# T04_Main_Board.net
KiCad netlist of a schematic drawn in EAGLE
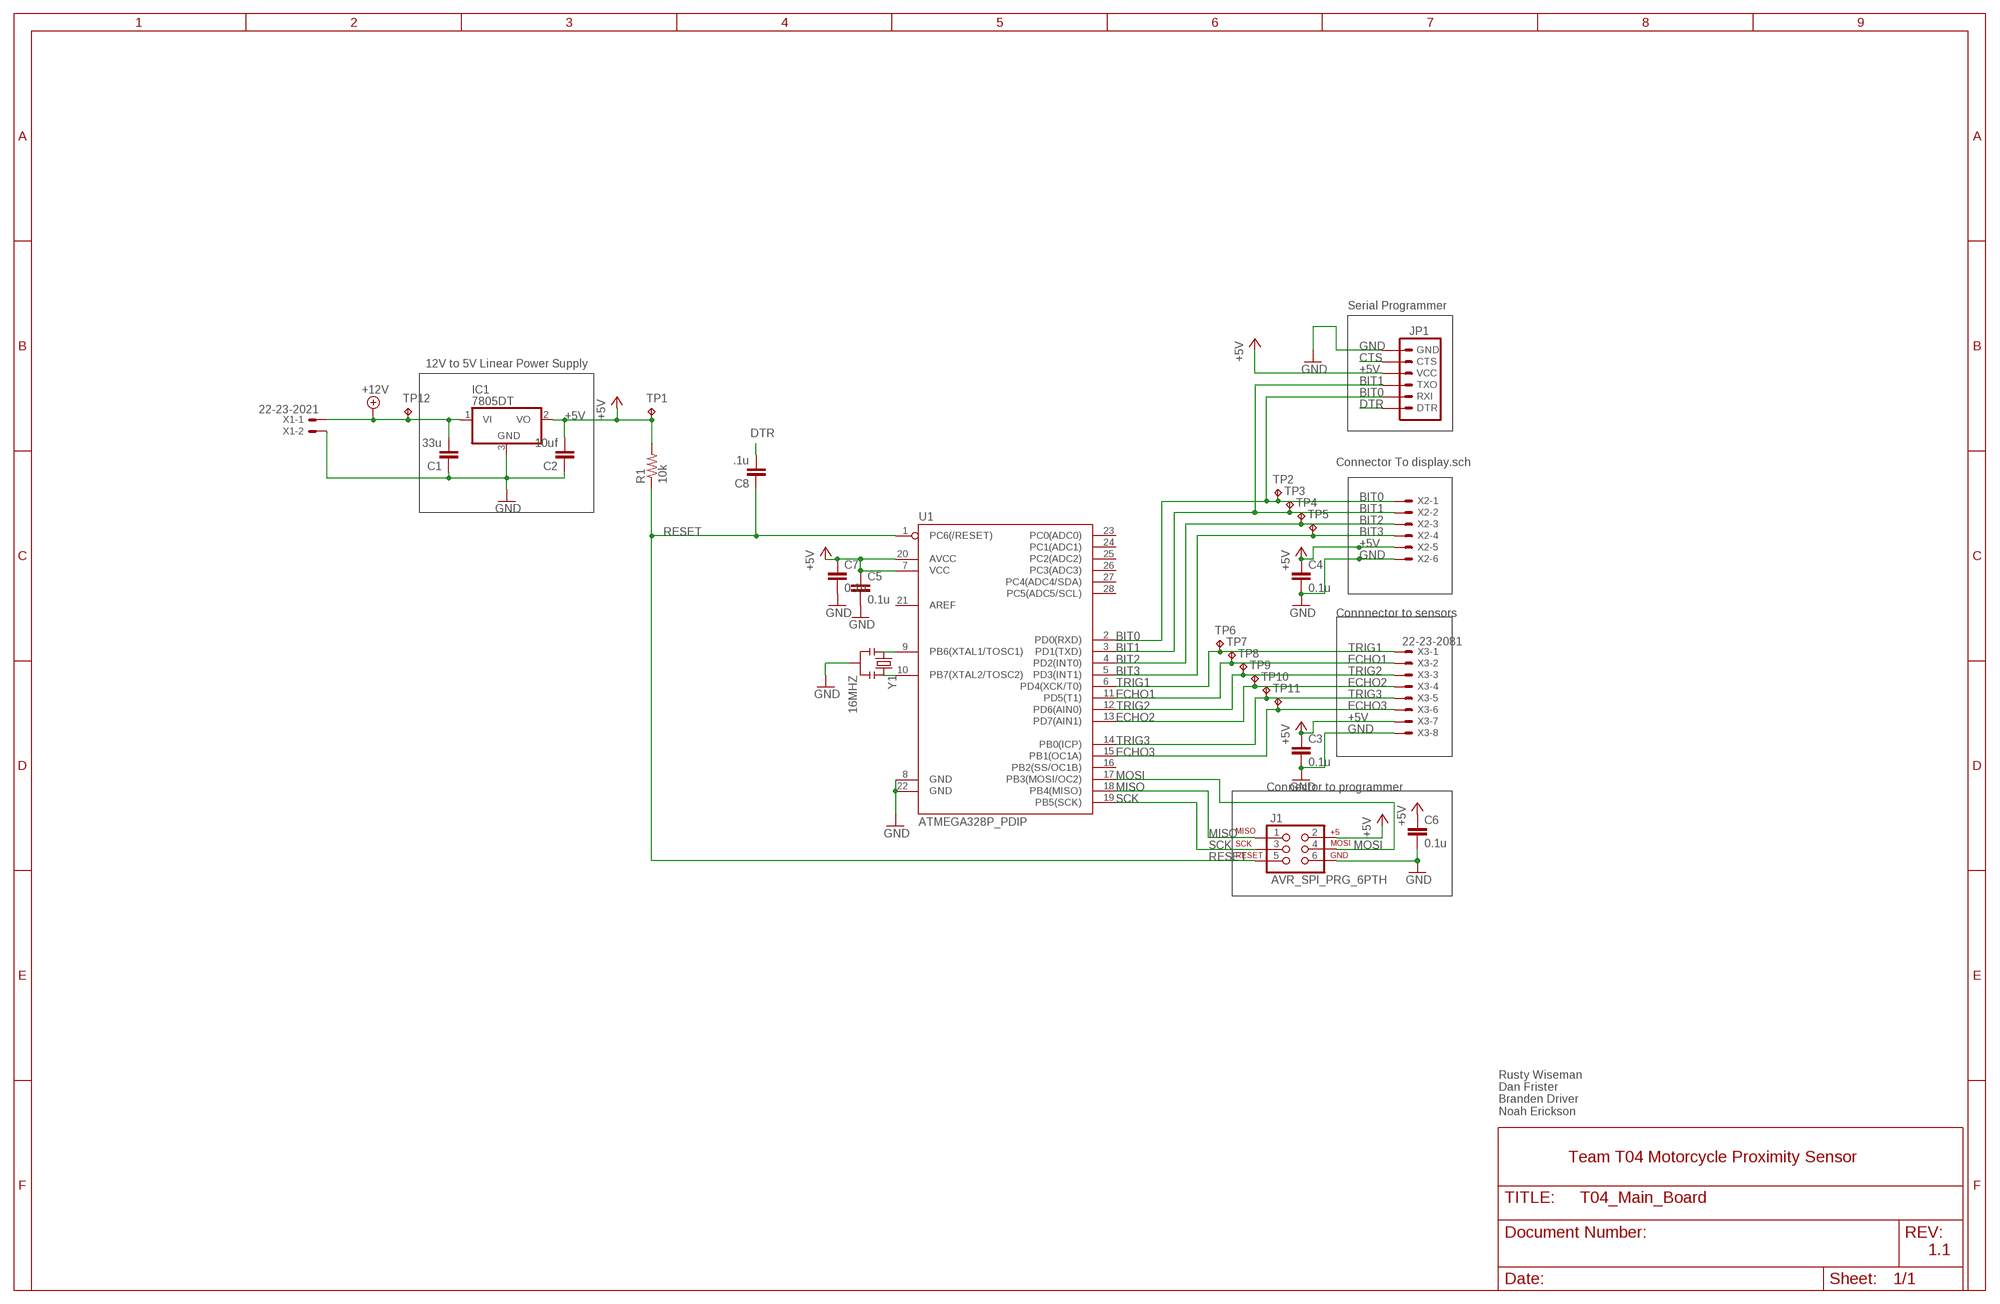
[diagram p0: schematic, sheet 1]

(export (version "E")
  (design (tool "Eeschema 10.0.6"))
  (components
    (comp (ref "C1")
      (value "33u")
      (footprint "eagle-import:C025-024X044")
      (libsource (lib "eagle-import") (part "C-EU025-024X044"))
    )
    (comp (ref "C2")
      (value "10uf")
      (footprint "eagle-import:C025-024X044")
      (libsource (lib "eagle-import") (part "C-EU025-024X044"))
    )
    (comp (ref "C3")
      (value "0.1u")
      (footprint "eagle-import:C025-024X044")
      (libsource (lib "eagle-import") (part "C-EU025-024X044"))
    )
    (comp (ref "C4")
      (value "0.1u")
      (footprint "eagle-import:C025-024X044")
      (libsource (lib "eagle-import") (part "C-EU025-024X044"))
    )
    (comp (ref "C5")
      (value "0.1u")
      (footprint "eagle-import:C025-024X044")
      (libsource (lib "eagle-import") (part "C-EU025-024X044"))
    )
    (comp (ref "C6")
      (value "0.1u")
      (footprint "eagle-import:C025-024X044")
      (libsource (lib "eagle-import") (part "C-EU025-024X044"))
    )
    (comp (ref "C7")
      (value "0.1u")
      (footprint "eagle-import:C025-024X044")
      (libsource (lib "eagle-import") (part "C-EU025-024X044"))
    )
    (comp (ref "C8")
      (value ".1u")
      (footprint "eagle-import:C025-024X044")
      (libsource (lib "eagle-import") (part "C-EU025-024X044"))
    )
    (comp (ref "IC1")
      (value "7805DT")
      (footprint "eagle-import:TO252")
      (libsource (lib "eagle-import") (part "78DT05"))
    )
    (comp (ref "J1")
      (value "AVR_SPI_PRG_6PTH")
      (footprint "eagle-import:2X3")
      (libsource (lib "eagle-import") (part "AVR_SPI_PRG_6PTH"))
    )
    (comp (ref "JP1")
      (value "ARDUINO_SERIAL_PROGRAMSMD")
      (footprint "eagle-import:1X06-SMD")
      (libsource (lib "eagle-import") (part "ARDUINO_SERIAL_PROGRAMSMD"))
    )
    (comp (ref "R1")
      (value "10k")
      (footprint "eagle-import:M2309")
      (libsource (lib "eagle-import") (part "R-US_M2309"))
    )
    (comp (ref "TP1")
      (value "TPB1,27")
      (footprint "eagle-import:B1,27")
      (libsource (lib "eagle-import") (part "TPB1,27"))
    )
    (comp (ref "TP2")
      (value "TPB1,27")
      (footprint "eagle-import:B1,27")
      (libsource (lib "eagle-import") (part "TPB1,27"))
    )
    (comp (ref "TP3")
      (value "TPB1,27")
      (footprint "eagle-import:B1,27")
      (libsource (lib "eagle-import") (part "TPB1,27"))
    )
    (comp (ref "TP4")
      (value "TPB1,27")
      (footprint "eagle-import:B1,27")
      (libsource (lib "eagle-import") (part "TPB1,27"))
    )
    (comp (ref "TP5")
      (value "TPB1,27")
      (footprint "eagle-import:B1,27")
      (libsource (lib "eagle-import") (part "TPB1,27"))
    )
    (comp (ref "TP6")
      (value "TPB1,27")
      (footprint "eagle-import:B1,27")
      (libsource (lib "eagle-import") (part "TPB1,27"))
    )
    (comp (ref "TP7")
      (value "TPB1,27")
      (footprint "eagle-import:B1,27")
      (libsource (lib "eagle-import") (part "TPB1,27"))
    )
    (comp (ref "TP8")
      (value "TPB1,27")
      (footprint "eagle-import:B1,27")
      (libsource (lib "eagle-import") (part "TPB1,27"))
    )
    (comp (ref "TP9")
      (value "TPB1,27")
      (footprint "eagle-import:B1,27")
      (libsource (lib "eagle-import") (part "TPB1,27"))
    )
    (comp (ref "TP10")
      (value "TPB1,27")
      (footprint "eagle-import:B1,27")
      (libsource (lib "eagle-import") (part "TPB1,27"))
    )
    (comp (ref "TP11")
      (value "TPB1,27")
      (footprint "eagle-import:B1,27")
      (libsource (lib "eagle-import") (part "TPB1,27"))
    )
    (comp (ref "TP12")
      (value "TPB1,27")
      (footprint "eagle-import:B1,27")
      (libsource (lib "eagle-import") (part "TPB1,27"))
    )
    (comp (ref "U1")
      (value "ATMEGA328P_PDIP")
      (footprint "eagle-import:DIL28-3")
      (libsource (lib "eagle-import") (part "ATMEGA328P_PDIP"))
    )
    (comp (ref "X1")
      (value "22-23-2021")
      (footprint "eagle-import:22-23-2021")
      (fields (field (name "MF") "MOLEX"))
      (libsource (lib "eagle-import") (part "22-23-2021"))
    )
    (comp (ref "X2")
      (value "22-23-2061")
      (footprint "eagle-import:22-23-2061")
      (fields (field (name "MF") "MOLEX"))
      (libsource (lib "eagle-import") (part "22-23-2061"))
    )
    (comp (ref "X3")
      (value "22-23-2081")
      (footprint "eagle-import:22-23-2081")
      (fields (field (name "MF") "MOLEX"))
      (libsource (lib "eagle-import") (part "22-23-2081"))
    )
    (comp (ref "Y1")
      (value "16MHZ")
      (footprint "eagle-import:RESONATOR-SMD")
      (libsource (lib "eagle-import") (part "RESONATOR16MHZ"))
    )
  )
  (nets
    (net (code "1") (name "+5V") (class "Default")
      (node (ref "C2") (pin "2") (pinfunction "2_2") (pintype "passive"))
      (node (ref "C3") (pin "1") (pinfunction "1_1") (pintype "passive"))
      (node (ref "C4") (pin "1") (pinfunction "1_1") (pintype "passive"))
      (node (ref "C5") (pin "1") (pinfunction "1_1") (pintype "passive"))
      (node (ref "C6") (pin "1") (pinfunction "1_1") (pintype "passive"))
      (node (ref "C7") (pin "1") (pinfunction "1_1") (pintype "passive"))
      (node (ref "IC1") (pin "2") (pinfunction "VO_2") (pintype "passive"))
      (node (ref "J1") (pin "2") (pinfunction "2_2") (pintype "passive"))
      (node (ref "JP1") (pin "4") (pinfunction "VCC_4") (pintype "passive"))
      (node (ref "R1") (pin "2") (pinfunction "2_2") (pintype "passive"))
      (node (ref "TP1") (pin "TP") (pinfunction "TP_TP") (pintype "input"))
      (node (ref "U1") (pin "20") (pinfunction "AVCC_20") (pintype "bidirectional"))
      (node (ref "U1") (pin "7") (pinfunction "VCC_7") (pintype "bidirectional"))
      (node (ref "X2") (pin "5") (pinfunction "S_5") (pintype "passive"))
      (node (ref "X3") (pin "7") (pinfunction "S_7") (pintype "passive"))
    )
    (net (code "2") (name "+12V") (class "Default")
      (node (ref "C1") (pin "2") (pinfunction "2_2") (pintype "passive"))
      (node (ref "IC1") (pin "1") (pinfunction "VI_1") (pintype "input"))
      (node (ref "TP12") (pin "TP") (pinfunction "TP_TP") (pintype "input"))
      (node (ref "X1") (pin "1") (pinfunction "S_1") (pintype "passive"))
    )
    (net (code "3") (name "/BIT0") (class "Default")
      (node (ref "JP1") (pin "2") (pinfunction "RXI_2") (pintype "passive"))
      (node (ref "TP2") (pin "TP") (pinfunction "TP_TP") (pintype "input"))
      (node (ref "U1") (pin "2") (pinfunction "PD0(RXD)_2") (pintype "bidirectional"))
      (node (ref "X2") (pin "1") (pinfunction "S_1") (pintype "passive"))
    )
    (net (code "4") (name "/BIT1") (class "Default")
      (node (ref "JP1") (pin "3") (pinfunction "TXO_3") (pintype "passive"))
      (node (ref "TP3") (pin "TP") (pinfunction "TP_TP") (pintype "input"))
      (node (ref "U1") (pin "3") (pinfunction "PD1(TXD)_3") (pintype "bidirectional"))
      (node (ref "X2") (pin "2") (pinfunction "S_2") (pintype "passive"))
    )
    (net (code "5") (name "/BIT2") (class "Default")
      (node (ref "TP4") (pin "TP") (pinfunction "TP_TP") (pintype "input"))
      (node (ref "U1") (pin "4") (pinfunction "PD2(INT0)_4") (pintype "bidirectional"))
      (node (ref "X2") (pin "3") (pinfunction "S_3") (pintype "passive"))
    )
    (net (code "6") (name "/BIT3") (class "Default")
      (node (ref "TP5") (pin "TP") (pinfunction "TP_TP") (pintype "input"))
      (node (ref "U1") (pin "5") (pinfunction "PD3(INT1)_5") (pintype "bidirectional"))
      (node (ref "X2") (pin "4") (pinfunction "S_4") (pintype "passive"))
    )
    (net (code "7") (name "/CTS") (class "Default")
      (node (ref "JP1") (pin "5") (pinfunction "CTS_5") (pintype "passive"))
    )
    (net (code "8") (name "/DTR") (class "Default")
      (node (ref "C8") (pin "2") (pinfunction "2_2") (pintype "passive"))
      (node (ref "JP1") (pin "1") (pinfunction "DTR_1") (pintype "passive"))
    )
    (net (code "9") (name "/ECHO1") (class "Default")
      (node (ref "TP7") (pin "TP") (pinfunction "TP_TP") (pintype "input"))
      (node (ref "U1") (pin "11") (pinfunction "PD5(T1)_11") (pintype "bidirectional"))
      (node (ref "X3") (pin "2") (pinfunction "S_2") (pintype "passive"))
    )
    (net (code "10") (name "/ECHO2") (class "Default")
      (node (ref "TP9") (pin "TP") (pinfunction "TP_TP") (pintype "input"))
      (node (ref "U1") (pin "13") (pinfunction "PD7(AIN1)_13") (pintype "bidirectional"))
      (node (ref "X3") (pin "4") (pinfunction "S_4") (pintype "passive"))
    )
    (net (code "11") (name "/ECHO3") (class "Default")
      (node (ref "TP11") (pin "TP") (pinfunction "TP_TP") (pintype "input"))
      (node (ref "U1") (pin "15") (pinfunction "PB1(OC1A)_15") (pintype "bidirectional"))
      (node (ref "X3") (pin "6") (pinfunction "S_6") (pintype "passive"))
    )
    (net (code "12") (name "/MISO") (class "Default")
      (node (ref "J1") (pin "1") (pinfunction "1_1") (pintype "passive"))
      (node (ref "U1") (pin "18") (pinfunction "PB4(MISO)_18") (pintype "bidirectional"))
    )
    (net (code "13") (name "/MOSI") (class "Default")
      (node (ref "J1") (pin "4") (pinfunction "4_4") (pintype "passive"))
      (node (ref "U1") (pin "17") (pinfunction "PB3(MOSI/OC2)_17") (pintype "bidirectional"))
    )
    (net (code "14") (name "/RESET") (class "Default")
      (node (ref "C8") (pin "1") (pinfunction "1_1") (pintype "passive"))
      (node (ref "J1") (pin "5") (pinfunction "5_5") (pintype "passive"))
      (node (ref "R1") (pin "1") (pinfunction "1_1") (pintype "passive"))
      (node (ref "U1") (pin "1") (pinfunction "PC6(/RESET)_1") (pintype "bidirectional"))
    )
    (net (code "15") (name "/SCK") (class "Default")
      (node (ref "J1") (pin "3") (pinfunction "3_3") (pintype "passive"))
      (node (ref "U1") (pin "19") (pinfunction "PB5(SCK)_19") (pintype "bidirectional"))
    )
    (net (code "16") (name "/TRIG1") (class "Default")
      (node (ref "TP6") (pin "TP") (pinfunction "TP_TP") (pintype "input"))
      (node (ref "U1") (pin "6") (pinfunction "PD4(XCK/T0)_6") (pintype "bidirectional"))
      (node (ref "X3") (pin "1") (pinfunction "S_1") (pintype "passive"))
    )
    (net (code "17") (name "/TRIG2") (class "Default")
      (node (ref "TP8") (pin "TP") (pinfunction "TP_TP") (pintype "input"))
      (node (ref "U1") (pin "12") (pinfunction "PD6(AIN0)_12") (pintype "bidirectional"))
      (node (ref "X3") (pin "3") (pinfunction "S_3") (pintype "passive"))
    )
    (net (code "18") (name "/TRIG3") (class "Default")
      (node (ref "TP10") (pin "TP") (pinfunction "TP_TP") (pintype "input"))
      (node (ref "U1") (pin "14") (pinfunction "PB0(ICP)_14") (pintype "bidirectional"))
      (node (ref "X3") (pin "5") (pinfunction "S_5") (pintype "passive"))
    )
    (net (code "19") (name "GND") (class "Default")
      (node (ref "C1") (pin "1") (pinfunction "1_1") (pintype "passive"))
      (node (ref "C2") (pin "1") (pinfunction "1_1") (pintype "passive"))
      (node (ref "C3") (pin "2") (pinfunction "2_2") (pintype "passive"))
      (node (ref "C4") (pin "2") (pinfunction "2_2") (pintype "passive"))
      (node (ref "C5") (pin "2") (pinfunction "2_2") (pintype "passive"))
      (node (ref "C6") (pin "2") (pinfunction "2_2") (pintype "passive"))
      (node (ref "C7") (pin "2") (pinfunction "2_2") (pintype "passive"))
      (node (ref "IC1") (pin "3") (pinfunction "GND_3") (pintype "passive"))
      (node (ref "J1") (pin "6") (pinfunction "6_6") (pintype "passive"))
      (node (ref "JP1") (pin "6") (pinfunction "GND_6") (pintype "passive"))
      (node (ref "U1") (pin "22") (pinfunction "GND_22") (pintype "bidirectional"))
      (node (ref "U1") (pin "8") (pinfunction "GND_8") (pintype "bidirectional"))
      (node (ref "X1") (pin "2") (pinfunction "S_2") (pintype "passive"))
      (node (ref "X2") (pin "6") (pinfunction "S_6") (pintype "passive"))
      (node (ref "X3") (pin "8") (pinfunction "S_8") (pintype "passive"))
      (node (ref "Y1") (pin "2") (pinfunction "2_2") (pintype "passive"))
    )
    (net (code "20") (name "Net-(U1-PB6(XTAL1{slash}TOSC1))") (class "Default")
      (node (ref "U1") (pin "9") (pinfunction "PB6(XTAL1/TOSC1)_9") (pintype "bidirectional"))
      (node (ref "Y1") (pin "1") (pinfunction "1_1") (pintype "passive"))
    )
    (net (code "21") (name "Net-(U1-PB7(XTAL2{slash}TOSC2))") (class "Default")
      (node (ref "U1") (pin "10") (pinfunction "PB7(XTAL2/TOSC2)_10") (pintype "bidirectional"))
      (node (ref "Y1") (pin "3") (pinfunction "3_3") (pintype "passive"))
    )
    (net (code "22") (name "unconnected-(U1-AREF-Pad21)") (class "Default")
      (node (ref "U1") (pin "21") (pinfunction "AREF_21") (pintype "bidirectional"))
    )
    (net (code "23") (name "unconnected-(U1-PB2(SS{slash}OC1B)-Pad16)") (class "Default")
      (node (ref "U1") (pin "16") (pinfunction "PB2(SS/OC1B)_16") (pintype "bidirectional"))
    )
    (net (code "24") (name "unconnected-(U1-PC0(ADC0)-Pad23)") (class "Default")
      (node (ref "U1") (pin "23") (pinfunction "PC0(ADC0)_23") (pintype "bidirectional"))
    )
    (net (code "25") (name "unconnected-(U1-PC1(ADC1)-Pad24)") (class "Default")
      (node (ref "U1") (pin "24") (pinfunction "PC1(ADC1)_24") (pintype "bidirectional"))
    )
    (net (code "26") (name "unconnected-(U1-PC2(ADC2)-Pad25)") (class "Default")
      (node (ref "U1") (pin "25") (pinfunction "PC2(ADC2)_25") (pintype "bidirectional"))
    )
    (net (code "27") (name "unconnected-(U1-PC3(ADC3)-Pad26)") (class "Default")
      (node (ref "U1") (pin "26") (pinfunction "PC3(ADC3)_26") (pintype "bidirectional"))
    )
    (net (code "28") (name "unconnected-(U1-PC4(ADC4{slash}SDA)-Pad27)") (class "Default")
      (node (ref "U1") (pin "27") (pinfunction "PC4(ADC4/SDA)_27") (pintype "bidirectional"))
    )
    (net (code "29") (name "unconnected-(U1-PC5(ADC5{slash}SCL)-Pad28)") (class "Default")
      (node (ref "U1") (pin "28") (pinfunction "PC5(ADC5/SCL)_28") (pintype "bidirectional"))
    )
  )
)
